# Sheet_V0_1_0.net
KiCad netlist of a schematic drawn in Altium Designer
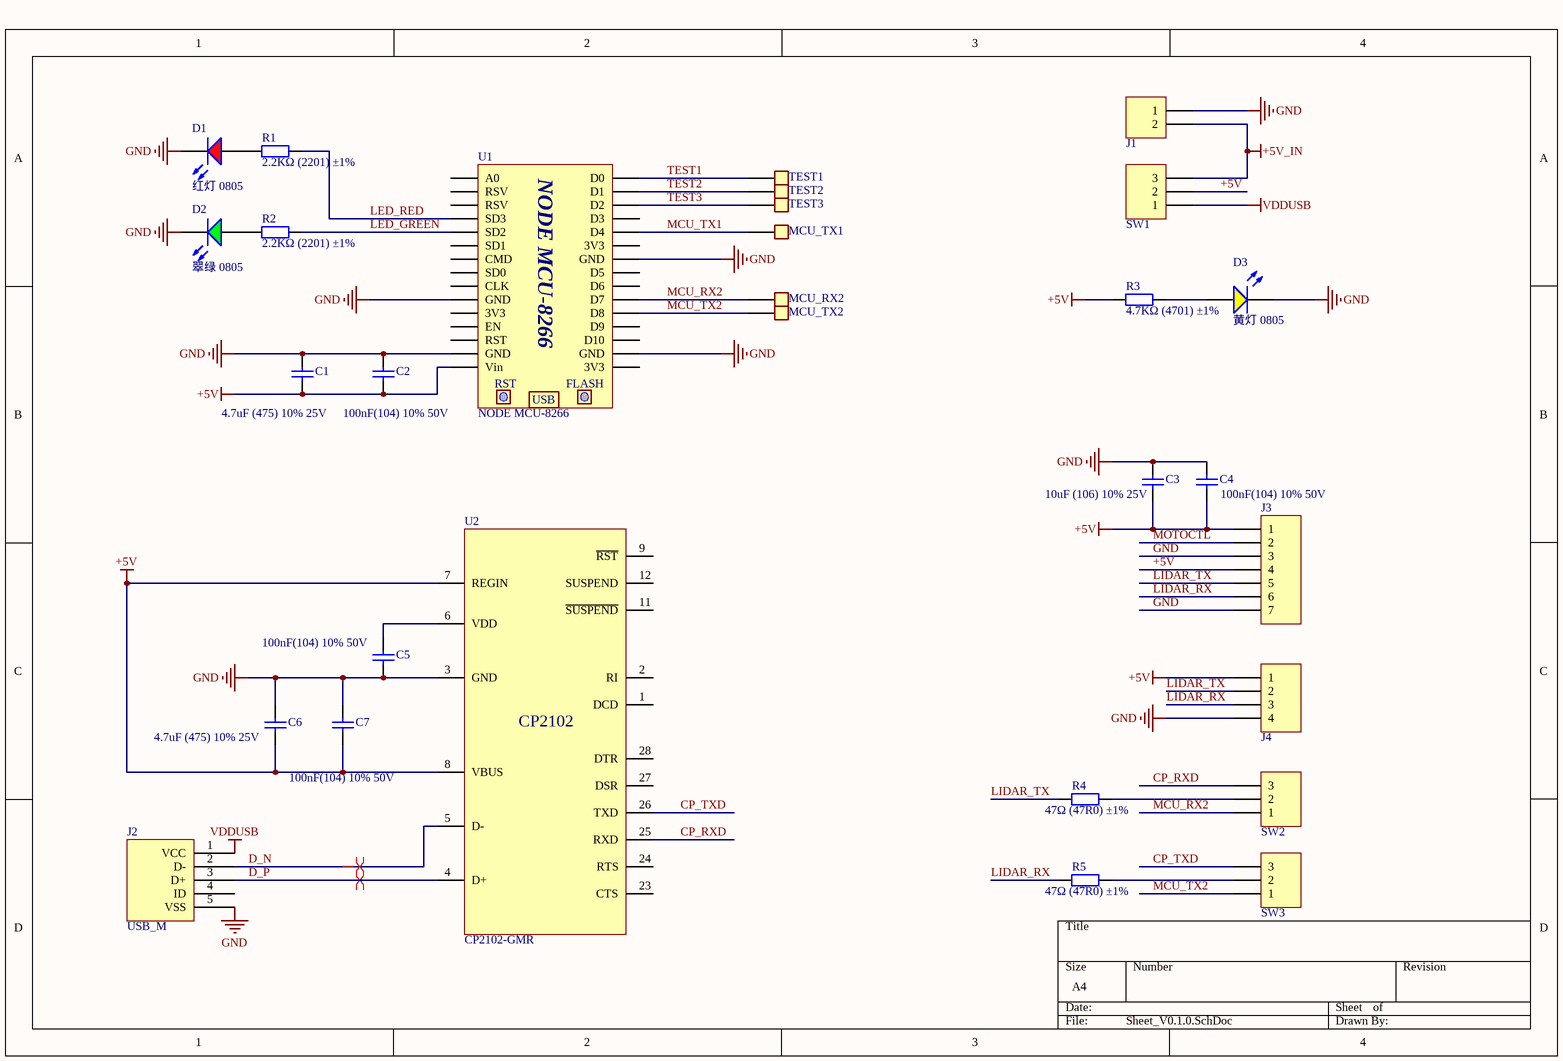
[diagram p0: Sheet_V0.1.0.SchDoc]

(export (version "E")
  (design (tool "Eeschema 10.0.6"))
  (components
    (comp (ref "C1")
      (value "4.7uF (475) 10% 25V")
      (footprint "0805_C")
      (description "贴片电容")
      (libsource (lib "Cap") (part "0805 4.7uF (475) 10% 25V"))
    )
    (comp (ref "C2")
      (value "100nF(104) 10% 50V")
      (footprint "0805_C")
      (description "贴片电容")
      (libsource (lib "Cap") (part "0805 100nF(104) 10% 50V"))
    )
    (comp (ref "C3")
      (value "10uF (106) 10% 25V")
      (footprint "0805_C")
      (description "贴片电容")
      (libsource (lib "Cap") (part "0805 10uF (106) 10% 25V"))
    )
    (comp (ref "C4")
      (value "100nF(104) 10% 50V")
      (footprint "0805_C")
      (description "贴片电容")
      (libsource (lib "Cap") (part "0805 100nF(104) 10% 50V"))
    )
    (comp (ref "C5")
      (value "100nF(104) 10% 50V")
      (footprint "0805_C")
      (description "贴片电容")
      (libsource (lib "Cap") (part "0805 100nF(104) 10% 50V"))
    )
    (comp (ref "C6")
      (value "4.7uF (475) 10% 25V")
      (footprint "0805_C")
      (description "贴片电容")
      (libsource (lib "Cap") (part "0805 4.7uF (475) 10% 25V"))
    )
    (comp (ref "C7")
      (value "100nF(104) 10% 50V")
      (footprint "0805_C")
      (description "贴片电容")
      (libsource (lib "Cap") (part "0805 100nF(104) 10% 50V"))
    )
    (comp (ref "D1")
      (value "红灯 0805")
      (footprint "0805_LED_S1")
      (description "发光二极管")
      (libsource (lib "LED") (part "0805 红灯"))
    )
    (comp (ref "D2")
      (value "翠绿 0805")
      (footprint "0805_LED_S1")
      (description "发光二极管")
      (libsource (lib "Miscellaneous Devices LC") (part "0805 翠绿"))
    )
    (comp (ref "D3")
      (value "黄灯 0805")
      (footprint "0805_LED_S1")
      (description "发光二极管")
      (libsource (lib "LED") (part "0805 黄灯"))
    )
    (comp (ref "J1")
      (value "Header 2")
      (footprint "HDR2X1_A")
      (description "接插件")
      (fields (field (name "PUBLISHER") "Altium Limited"))
      (libsource (lib "Miscellaneous Connectors") (part "Header 2"))
    )
    (comp (ref "J2")
      (value "USB_M")
      (footprint "USB-MICRO-A")
      (description "MicroUSB接口")
      (libsource (lib "ghzhang") (part "USB_M"))
    )
    (comp (ref "J3")
      (value "Header 7")
      (footprint "HDR1X7")
      (description "Header, 7-Pin")
      (fields (field (name "PUBLISHER") "Altium Limited"))
      (libsource (lib "Miscellaneous Connectors") (part "Header 7"))
    )
    (comp (ref "J4")
      (value "Header 4")
      (footprint "HDR4X1_A")
      (description "接插件")
      (fields (field (name "PUBLISHER") "Altium Limited"))
      (libsource (lib "Miscellaneous Connectors") (part "Header 4"))
    )
    (comp (ref "MCU_RX2") (value "TP") (footprint "CHECK-A") (libsource (lib "原理图库") (part "TP")))
    (comp (ref "MCU_TX1") (value "TP") (footprint "CHECK-A") (libsource (lib "原理图库") (part "TP")))
    (comp (ref "MCU_TX2") (value "TP") (footprint "CHECK-A") (libsource (lib "原理图库") (part "TP")))
    (comp (ref "R1")
      (value "2.2KΩ (2201) ±1%")
      (footprint "0805_R")
      (description "贴片电阻")
      (libsource (lib "Miscellaneous Devices LC") (part "0805 2.2KΩ (2201) 1%"))
    )
    (comp (ref "R2")
      (value "2.2KΩ (2201) ±1%")
      (footprint "0805_R")
      (description "贴片电阻")
      (libsource (lib "Miscellaneous Devices LC") (part "0805 2.2KΩ (2201) 1%"))
    )
    (comp (ref "R3")
      (value "4.7KΩ (4701) ±1%")
      (footprint "0805_R")
      (description "贴片电阻")
      (libsource (lib "RES") (part "0805 4.7KΩ (4701) 1%"))
    )
    (comp (ref "R4")
      (value "47Ω (47R0) ±1%")
      (footprint "0805_R")
      (description "贴片电阻")
      (libsource (lib "RES") (part "0805 47Ω (47R0) 1%"))
    )
    (comp (ref "R5")
      (value "47Ω (47R0) ±1%")
      (footprint "0805_R")
      (description "贴片电阻")
      (libsource (lib "RES") (part "0805 47Ω (47R0) 1%"))
    )
    (comp (ref "SW1")
      (value "Header 3")
      (footprint "HDR3X1_A")
      (description "接插件")
      (fields (field (name "PUBLISHER") "Altium Limited"))
      (libsource (lib "Miscellaneous Connectors") (part "Header 3"))
    )
    (comp (ref "SW2")
      (value "Header 3")
      (footprint "HDR3X1_A")
      (description "接插件")
      (fields (field (name "PUBLISHER") "Altium Limited"))
      (libsource (lib "") (part "Header 3_1"))
    )
    (comp (ref "SW3")
      (value "Header 3")
      (footprint "HDR3X1_A")
      (description "接插件")
      (fields (field (name "PUBLISHER") "Altium Limited"))
      (libsource (lib "") (part "Header 3_1"))
    )
    (comp (ref "TEST1") (value "TP") (footprint "CHECK-A") (libsource (lib "原理图库") (part "TP")))
    (comp (ref "TEST2") (value "TP") (footprint "CHECK-A") (libsource (lib "原理图库") (part "TP")))
    (comp (ref "TEST3") (value "TP") (footprint "CHECK-A") (libsource (lib "原理图库") (part "TP")))
    (comp (ref "U1") (value "NODE MCU-8266") (libsource (lib "ghzhang") (part "NodeMCU_8266")))
    (comp (ref "U2")
      (value "CP2102-GMR")
      (footprint "QFN-28_5x5x05P")
      (description "USB")
      (libsource (lib "IC") (part "CP2102-GMR_[C6568]"))
    )
  )
  (nets
    (net (code "1") (name "+5V") (class "Default")
      (node (ref "C1") (pin "1") (pinfunction "1_1") (pintype "passive"))
      (node (ref "C2") (pin "1") (pinfunction "1_1") (pintype "passive"))
      (node (ref "C3") (pin "1") (pinfunction "1_1") (pintype "passive"))
      (node (ref "C4") (pin "1") (pinfunction "1_1") (pintype "passive"))
      (node (ref "C6") (pin "1") (pinfunction "1_1") (pintype "passive"))
      (node (ref "C7") (pin "1") (pinfunction "1_1") (pintype "passive"))
      (node (ref "J3") (pin "1") (pinfunction "1_1") (pintype "passive"))
      (node (ref "J3") (pin "4") (pinfunction "4_4") (pintype "passive"))
      (node (ref "J4") (pin "1") (pinfunction "1_1") (pintype "passive"))
      (node (ref "R3") (pin "1") (pinfunction "1_1") (pintype "passive"))
      (node (ref "SW1") (pin "2") (pinfunction "2_2") (pintype "passive"))
      (node (ref "U1") (pin "15") (pinfunction "Vin_15") (pintype "passive"))
      (node (ref "U2") (pin "7") (pinfunction "REGIN_7") (pintype "passive"))
      (node (ref "U2") (pin "8") (pinfunction "VBUS_8") (pintype "passive"))
    )
    (net (code "2") (name "+5V_IN") (class "Default")
      (node (ref "J1") (pin "2") (pinfunction "2_2") (pintype "passive"))
      (node (ref "SW1") (pin "3") (pinfunction "3_3") (pintype "passive"))
    )
    (net (code "3") (name "/CP_RXD") (class "Default")
      (node (ref "SW2") (pin "3") (pinfunction "3_3") (pintype "passive"))
      (node (ref "U2") (pin "25") (pinfunction "RXD_25") (pintype "passive"))
    )
    (net (code "4") (name "/CP_TXD") (class "Default")
      (node (ref "SW3") (pin "3") (pinfunction "3_3") (pintype "passive"))
      (node (ref "U2") (pin "26") (pinfunction "TXD_26") (pintype "passive"))
    )
    (net (code "5") (name "/D_N") (class "Default")
      (node (ref "J2") (pin "2") (pinfunction "D-_2") (pintype "passive"))
      (node (ref "U2") (pin "5") (pinfunction "D-_5") (pintype "passive"))
    )
    (net (code "6") (name "/D_P") (class "Default")
      (node (ref "J2") (pin "3") (pinfunction "D+_3") (pintype "passive"))
      (node (ref "U2") (pin "4") (pinfunction "D+_4") (pintype "passive"))
    )
    (net (code "7") (name "/LED_GREEN") (class "Default")
      (node (ref "R2") (pin "1") (pinfunction "1_1") (pintype "passive"))
      (node (ref "U1") (pin "5") (pinfunction "SD2_5") (pintype "passive"))
    )
    (net (code "8") (name "/LED_RED") (class "Default")
      (node (ref "R1") (pin "1") (pinfunction "1_1") (pintype "passive"))
      (node (ref "U1") (pin "4") (pinfunction "SD3_4") (pintype "passive"))
    )
    (net (code "9") (name "/LIDAR_RX") (class "Default")
      (node (ref "J3") (pin "6") (pinfunction "6_6") (pintype "passive"))
      (node (ref "J4") (pin "3") (pinfunction "3_3") (pintype "passive"))
      (node (ref "R5") (pin "1") (pinfunction "1_1") (pintype "passive"))
    )
    (net (code "10") (name "/LIDAR_TX") (class "Default")
      (node (ref "J3") (pin "5") (pinfunction "5_5") (pintype "passive"))
      (node (ref "J4") (pin "2") (pinfunction "2_2") (pintype "passive"))
      (node (ref "R4") (pin "1") (pinfunction "1_1") (pintype "passive"))
    )
    (net (code "11") (name "/MCU_RX2") (class "Default")
      (node (ref "MCU_RX2") (pin "1") (pintype "passive"))
      (node (ref "SW2") (pin "1") (pinfunction "1_1") (pintype "passive"))
      (node (ref "U1") (pin "21") (pinfunction "D7_21") (pintype "passive"))
    )
    (net (code "12") (name "/MCU_TX1") (class "Default")
      (node (ref "MCU_TX1") (pin "1") (pintype "passive"))
      (node (ref "U1") (pin "26") (pinfunction "D4_26") (pintype "passive"))
    )
    (net (code "13") (name "/MCU_TX2") (class "Default")
      (node (ref "MCU_TX2") (pin "1") (pintype "passive"))
      (node (ref "SW3") (pin "1") (pinfunction "1_1") (pintype "passive"))
      (node (ref "U1") (pin "20") (pinfunction "D8_20") (pintype "passive"))
    )
    (net (code "14") (name "/MOTOCTL") (class "Default")
      (node (ref "J3") (pin "2") (pinfunction "2_2") (pintype "passive"))
    )
    (net (code "15") (name "/TEST1") (class "Default")
      (node (ref "TEST1") (pin "1") (pintype "passive"))
      (node (ref "U1") (pin "30") (pinfunction "D0_30") (pintype "passive"))
    )
    (net (code "16") (name "/TEST2") (class "Default")
      (node (ref "TEST2") (pin "1") (pintype "passive"))
      (node (ref "U1") (pin "29") (pinfunction "D1_29") (pintype "passive"))
    )
    (net (code "17") (name "/TEST3") (class "Default")
      (node (ref "TEST3") (pin "1") (pintype "passive"))
      (node (ref "U1") (pin "28") (pinfunction "D2_28") (pintype "passive"))
    )
    (net (code "18") (name "GND") (class "Default")
      (node (ref "C1") (pin "2") (pinfunction "2_2") (pintype "passive"))
      (node (ref "C2") (pin "2") (pinfunction "2_2") (pintype "passive"))
      (node (ref "C3") (pin "2") (pinfunction "2_2") (pintype "passive"))
      (node (ref "C4") (pin "2") (pinfunction "2_2") (pintype "passive"))
      (node (ref "C5") (pin "1") (pinfunction "1_1") (pintype "passive"))
      (node (ref "C6") (pin "2") (pinfunction "2_2") (pintype "passive"))
      (node (ref "C7") (pin "2") (pinfunction "2_2") (pintype "passive"))
      (node (ref "D1") (pin "K") (pinfunction "K_K") (pintype "passive"))
      (node (ref "D2") (pin "K") (pinfunction "K_K") (pintype "passive"))
      (node (ref "D3") (pin "K") (pinfunction "K_K") (pintype "passive"))
      (node (ref "J1") (pin "1") (pinfunction "1_1") (pintype "passive"))
      (node (ref "J2") (pin "5") (pinfunction "VSS_5") (pintype "passive"))
      (node (ref "J3") (pin "3") (pinfunction "3_3") (pintype "passive"))
      (node (ref "J3") (pin "7") (pinfunction "7_7") (pintype "passive"))
      (node (ref "J4") (pin "4") (pinfunction "4_4") (pintype "passive"))
      (node (ref "U1") (pin "10") (pinfunction "GND_10") (pintype "passive"))
      (node (ref "U1") (pin "14") (pinfunction "GND_14") (pintype "passive"))
      (node (ref "U1") (pin "17") (pinfunction "GND_17") (pintype "passive"))
      (node (ref "U1") (pin "24") (pinfunction "GND_24") (pintype "passive"))
      (node (ref "U2") (pin "3") (pinfunction "GND_3") (pintype "passive"))
    )
    (net (code "19") (name "Net-(D1-PadA)") (class "Default")
      (node (ref "D1") (pin "A") (pinfunction "A_A") (pintype "passive"))
      (node (ref "R1") (pin "2") (pinfunction "2_2") (pintype "passive"))
    )
    (net (code "20") (name "Net-(D2-PadA)") (class "Default")
      (node (ref "D2") (pin "A") (pinfunction "A_A") (pintype "passive"))
      (node (ref "R2") (pin "2") (pinfunction "2_2") (pintype "passive"))
    )
    (net (code "21") (name "Net-(D3-PadA)") (class "Default")
      (node (ref "D3") (pin "A") (pinfunction "A_A") (pintype "passive"))
      (node (ref "R3") (pin "2") (pinfunction "2_2") (pintype "passive"))
    )
    (net (code "22") (name "Net-(R4-Pad2)") (class "Default")
      (node (ref "R4") (pin "2") (pinfunction "2_2") (pintype "passive"))
      (node (ref "SW2") (pin "2") (pinfunction "2_2") (pintype "passive"))
    )
    (net (code "23") (name "Net-(R5-Pad2)") (class "Default")
      (node (ref "R5") (pin "2") (pinfunction "2_2") (pintype "passive"))
      (node (ref "SW3") (pin "2") (pinfunction "2_2") (pintype "passive"))
    )
    (net (code "24") (name "Net-(U2-VDD)") (class "Default")
      (node (ref "C5") (pin "2") (pinfunction "2_2") (pintype "passive"))
      (node (ref "U2") (pin "6") (pinfunction "VDD_6") (pintype "passive"))
    )
    (net (code "25") (name "VDDUSB") (class "Default")
      (node (ref "J2") (pin "1") (pinfunction "VCC_1") (pintype "passive"))
      (node (ref "SW1") (pin "1") (pinfunction "1_1") (pintype "passive"))
    )
    (net (code "26") (name "unconnected-(J2-ID-Pad4)") (class "Default")
      (node (ref "J2") (pin "4") (pinfunction "ID_4") (pintype "passive"))
    )
    (net (code "27") (name "unconnected-(U1-3V3-Pad11)") (class "Default")
      (node (ref "U1") (pin "11") (pinfunction "3V3_11") (pintype "passive"))
    )
    (net (code "28") (name "unconnected-(U1-3V3-Pad16)") (class "Default")
      (node (ref "U1") (pin "16") (pinfunction "3V3_16") (pintype "passive"))
    )
    (net (code "29") (name "unconnected-(U1-3V3-Pad25)") (class "Default")
      (node (ref "U1") (pin "25") (pinfunction "3V3_25") (pintype "passive"))
    )
    (net (code "30") (name "unconnected-(U1-A0-Pad1)") (class "Default")
      (node (ref "U1") (pin "1") (pinfunction "A0_1") (pintype "passive"))
    )
    (net (code "31") (name "unconnected-(U1-CLK-Pad9)") (class "Default")
      (node (ref "U1") (pin "9") (pinfunction "CLK_9") (pintype "passive"))
    )
    (net (code "32") (name "unconnected-(U1-CMD-Pad7)") (class "Default")
      (node (ref "U1") (pin "7") (pinfunction "CMD_7") (pintype "passive"))
    )
    (net (code "33") (name "unconnected-(U1-D3-Pad27)") (class "Default")
      (node (ref "U1") (pin "27") (pinfunction "D3_27") (pintype "passive"))
    )
    (net (code "34") (name "unconnected-(U1-D5-Pad23)") (class "Default")
      (node (ref "U1") (pin "23") (pinfunction "D5_23") (pintype "passive"))
    )
    (net (code "35") (name "unconnected-(U1-D6-Pad22)") (class "Default")
      (node (ref "U1") (pin "22") (pinfunction "D6_22") (pintype "passive"))
    )
    (net (code "36") (name "unconnected-(U1-D9-Pad19)") (class "Default")
      (node (ref "U1") (pin "19") (pinfunction "D9_19") (pintype "passive"))
    )
    (net (code "37") (name "unconnected-(U1-D10-Pad18)") (class "Default")
      (node (ref "U1") (pin "18") (pinfunction "D10_18") (pintype "passive"))
    )
    (net (code "38") (name "unconnected-(U1-EN-Pad12)") (class "Default")
      (node (ref "U1") (pin "12") (pinfunction "EN_12") (pintype "passive"))
    )
    (net (code "39") (name "unconnected-(U1-RST-Pad13)") (class "Default")
      (node (ref "U1") (pin "13") (pinfunction "RST_13") (pintype "passive"))
    )
    (net (code "40") (name "unconnected-(U1-RSV-Pad2)") (class "Default")
      (node (ref "U1") (pin "2") (pinfunction "RSV_2") (pintype "passive"))
    )
    (net (code "41") (name "unconnected-(U1-RSV-Pad3)") (class "Default")
      (node (ref "U1") (pin "3") (pinfunction "RSV_3") (pintype "passive"))
    )
    (net (code "42") (name "unconnected-(U1-SD0-Pad8)") (class "Default")
      (node (ref "U1") (pin "8") (pinfunction "SD0_8") (pintype "passive"))
    )
    (net (code "43") (name "unconnected-(U1-SD1-Pad6)") (class "Default")
      (node (ref "U1") (pin "6") (pinfunction "SD1_6") (pintype "passive"))
    )
    (net (code "44") (name "unconnected-(U2-CTS-Pad23)") (class "Default")
      (node (ref "U2") (pin "23") (pinfunction "CTS_23") (pintype "passive"))
    )
    (net (code "45") (name "unconnected-(U2-DCD-Pad1)") (class "Default")
      (node (ref "U2") (pin "1") (pinfunction "DCD_1") (pintype "passive"))
    )
    (net (code "46") (name "unconnected-(U2-DSR-Pad27)") (class "Default")
      (node (ref "U2") (pin "27") (pinfunction "DSR_27") (pintype "passive"))
    )
    (net (code "47") (name "unconnected-(U2-DTR-Pad28)") (class "Default")
      (node (ref "U2") (pin "28") (pinfunction "DTR_28") (pintype "passive"))
    )
    (net (code "48") (name "unconnected-(U2-RI-Pad2)") (class "Default")
      (node (ref "U2") (pin "2") (pinfunction "RI_2") (pintype "passive"))
    )
    (net (code "49") (name "unconnected-(U2-RTS-Pad24)") (class "Default")
      (node (ref "U2") (pin "24") (pinfunction "RTS_24") (pintype "passive"))
    )
    (net (code "50") (name "unconnected-(U2-SUSPEND-Pad12)") (class "Default")
      (node (ref "U2") (pin "12") (pinfunction "SUSPEND_12") (pintype "passive"))
    )
    (net (code "51") (name "unconnected-(U2-~{RST}-Pad9)") (class "Default")
      (node (ref "U2") (pin "9") (pinfunction "~{RST}_9") (pintype "passive"))
    )
    (net (code "52") (name "unconnected-(U2-~{SUSPEND}-Pad11)") (class "Default")
      (node (ref "U2") (pin "11") (pinfunction "~{SUSPEND}_11") (pintype "passive"))
    )
  )
)
